# Line_Reader.net
KiCad netlist of a schematic drawn in Altium Designer
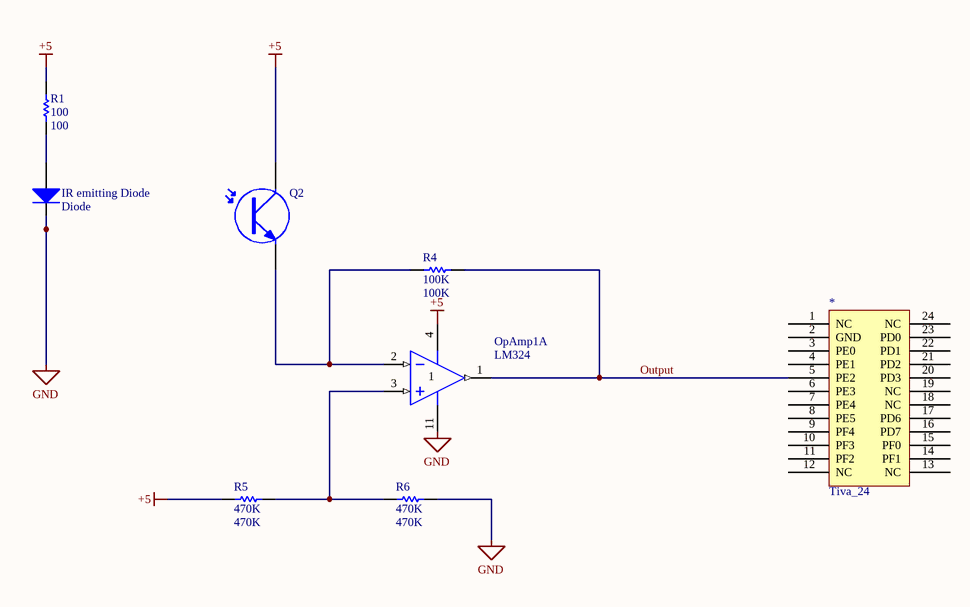
[diagram p0: Line  Reader.SchDoc]

(export (version "E")
  (design (tool "Eeschema 10.0.6"))
  (components
    (comp (ref "*")
      (value "Tiva_24")
      (description "Tiva Protection 24 Pin Connector")
      (libsource (lib "ME218_BaseLib") (part "Tiva_24"))
    )
    (comp (ref "IR emitting Diode")
      (value "Diode")
      (footprint "DSO-C2/X3.3")
      (description "Default Diode")
      (fields
        (field (name "MANUFACTURER") "Generic Components")
        (field (name "PUBLISHER") "Altium Hobart Technology Centre")
      )
      (libsource (lib "ME218_BaseLib") (part "Diode"))
    )
    (comp (ref "OpAmp1")
      (value "LM324")
      (footprint "DIP-14")
      (description "Low-Power Quad Operational Amplifier")
      (fields
        (field (name "MANUFACTURER") "National Semiconductor")
        (field (name "PUBLISHER") "Altium Hobart Technology Centre")
      )
      (libsource (lib "ME218_BaseLib") (part "LM324AJ"))
    )
    (comp (ref "Q2")
      (value "LTR 3208")
      (footprint "SFM-T2(3)/X1.6V")
      (description "NPN Phototransistor")
      (fields (field (name "MANUFACTURER") "Generic Components"))
      (libsource (lib "ME218_BaseLib") (part "Photo NPN"))
    )
    (comp (ref "R1")
      (value "100")
      (footprint "AXIAL-0.3")
      (description "Resistor")
      (fields
        (field (name "MANUFACTURER") "Generic Components")
        (field (name "ALTIUM_VALUE") "100")
        (field (name "PUBLISHER") "Altium Hobart Technology Centre")
      )
      (libsource (lib "ME218_BaseLib") (part "Res1"))
    )
    (comp (ref "R4")
      (value "100K")
      (footprint "AXIAL-0.3")
      (description "Resistor")
      (fields
        (field (name "MANUFACTURER") "Generic Components")
        (field (name "ALTIUM_VALUE") "100K")
        (field (name "PUBLISHER") "Altium Hobart Technology Centre")
      )
      (libsource (lib "ME218_BaseLib") (part "Res1"))
    )
    (comp (ref "R5")
      (value "470K")
      (footprint "AXIAL-0.3")
      (description "Resistor")
      (fields
        (field (name "MANUFACTURER") "Generic Components")
        (field (name "ALTIUM_VALUE") "470K")
        (field (name "PUBLISHER") "Altium Hobart Technology Centre")
      )
      (libsource (lib "ME218_BaseLib") (part "Res1"))
    )
    (comp (ref "R6")
      (value "470K")
      (footprint "AXIAL-0.3")
      (description "Resistor")
      (fields
        (field (name "MANUFACTURER") "Generic Components")
        (field (name "ALTIUM_VALUE") "470K")
        (field (name "PUBLISHER") "Altium Hobart Technology Centre")
      )
      (libsource (lib "ME218_BaseLib") (part "Res1"))
    )
  )
  (nets
    (net (code "1") (name "+5") (class "Default")
      (node (ref "OpAmp1") (pin "4") (pinfunction "V+_4") (pintype "power_in"))
      (node (ref "Q2") (pin "1") (pinfunction "C_1") (pintype "passive"))
      (node (ref "R1") (pin "2") (pinfunction "2_2") (pintype "passive"))
      (node (ref "R5") (pin "1") (pinfunction "1_1") (pintype "passive"))
    )
    (net (code "2") (name "/Output") (class "Default")
      (node (ref "*") (pin "5") (pinfunction "PE2_5") (pintype "passive"))
      (node (ref "OpAmp1") (pin "1") (pinfunction "OUT_1") (pintype "output"))
      (node (ref "R4") (pin "2") (pinfunction "2_2") (pintype "passive"))
    )
    (net (code "3") (name "GND") (class "Default")
      (node (ref "IR emitting Diode") (pin "2") (pinfunction "K_2") (pintype "passive"))
      (node (ref "OpAmp1") (pin "11") (pinfunction "GND_11") (pintype "power_in"))
      (node (ref "R6") (pin "2") (pinfunction "2_2") (pintype "passive"))
    )
    (net (code "4") (name "Net-(IR emitting Diode-A)") (class "Default")
      (node (ref "IR emitting Diode") (pin "1") (pinfunction "A_1") (pintype "passive"))
      (node (ref "R1") (pin "1") (pinfunction "1_1") (pintype "passive"))
    )
    (net (code "5") (name "Net-(OpAmp1A-IN+)") (class "Default")
      (node (ref "OpAmp1") (pin "3") (pinfunction "IN+_3") (pintype "input"))
      (node (ref "R5") (pin "2") (pinfunction "2_2") (pintype "passive"))
      (node (ref "R6") (pin "1") (pinfunction "1_1") (pintype "passive"))
    )
    (net (code "6") (name "Net-(OpAmp1A-IN-)") (class "Default")
      (node (ref "OpAmp1") (pin "2") (pinfunction "IN-_2") (pintype "input"))
      (node (ref "Q2") (pin "3") (pinfunction "E_3") (pintype "passive"))
      (node (ref "R4") (pin "1") (pinfunction "1_1") (pintype "passive"))
    )
    (net (code "7") (name "unconnected-(*-GND-Pad2)") (class "Default")
      (node (ref "*") (pin "2") (pinfunction "GND_2") (pintype "passive"))
    )
    (net (code "8") (name "unconnected-(*-NC-Pad1)") (class "Default")
      (node (ref "*") (pin "1") (pinfunction "NC_1") (pintype "passive"))
    )
    (net (code "9") (name "unconnected-(*-NC-Pad12)") (class "Default")
      (node (ref "*") (pin "12") (pinfunction "NC_12") (pintype "passive"))
    )
    (net (code "10") (name "unconnected-(*-NC-Pad13)") (class "Default")
      (node (ref "*") (pin "13") (pinfunction "NC_13") (pintype "passive"))
    )
    (net (code "11") (name "unconnected-(*-NC-Pad18)") (class "Default")
      (node (ref "*") (pin "18") (pinfunction "NC_18") (pintype "passive"))
    )
    (net (code "12") (name "unconnected-(*-NC-Pad19)") (class "Default")
      (node (ref "*") (pin "19") (pinfunction "NC_19") (pintype "passive"))
    )
    (net (code "13") (name "unconnected-(*-NC-Pad24)") (class "Default")
      (node (ref "*") (pin "24") (pinfunction "NC_24") (pintype "passive"))
    )
    (net (code "14") (name "unconnected-(*-PD0-Pad23)") (class "Default")
      (node (ref "*") (pin "23") (pinfunction "PD0_23") (pintype "passive"))
    )
    (net (code "15") (name "unconnected-(*-PD1-Pad22)") (class "Default")
      (node (ref "*") (pin "22") (pinfunction "PD1_22") (pintype "passive"))
    )
    (net (code "16") (name "unconnected-(*-PD2-Pad21)") (class "Default")
      (node (ref "*") (pin "21") (pinfunction "PD2_21") (pintype "passive"))
    )
    (net (code "17") (name "unconnected-(*-PD3-Pad20)") (class "Default")
      (node (ref "*") (pin "20") (pinfunction "PD3_20") (pintype "passive"))
    )
    (net (code "18") (name "unconnected-(*-PD6-Pad17)") (class "Default")
      (node (ref "*") (pin "17") (pinfunction "PD6_17") (pintype "passive"))
    )
    (net (code "19") (name "unconnected-(*-PD7-Pad16)") (class "Default")
      (node (ref "*") (pin "16") (pinfunction "PD7_16") (pintype "passive"))
    )
    (net (code "20") (name "unconnected-(*-PE0-Pad3)") (class "Default")
      (node (ref "*") (pin "3") (pinfunction "PE0_3") (pintype "passive"))
    )
    (net (code "21") (name "unconnected-(*-PE1-Pad4)") (class "Default")
      (node (ref "*") (pin "4") (pinfunction "PE1_4") (pintype "passive"))
    )
    (net (code "22") (name "unconnected-(*-PE3-Pad6)") (class "Default")
      (node (ref "*") (pin "6") (pinfunction "PE3_6") (pintype "passive"))
    )
    (net (code "23") (name "unconnected-(*-PE4-Pad7)") (class "Default")
      (node (ref "*") (pin "7") (pinfunction "PE4_7") (pintype "passive"))
    )
    (net (code "24") (name "unconnected-(*-PE5-Pad8)") (class "Default")
      (node (ref "*") (pin "8") (pinfunction "PE5_8") (pintype "passive"))
    )
    (net (code "25") (name "unconnected-(*-PF0-Pad15)") (class "Default")
      (node (ref "*") (pin "15") (pinfunction "PF0_15") (pintype "passive"))
    )
    (net (code "26") (name "unconnected-(*-PF1-Pad14)") (class "Default")
      (node (ref "*") (pin "14") (pinfunction "PF1_14") (pintype "passive"))
    )
    (net (code "27") (name "unconnected-(*-PF2-Pad11)") (class "Default")
      (node (ref "*") (pin "11") (pinfunction "PF2_11") (pintype "passive"))
    )
    (net (code "28") (name "unconnected-(*-PF3-Pad10)") (class "Default")
      (node (ref "*") (pin "10") (pinfunction "PF3_10") (pintype "passive"))
    )
    (net (code "29") (name "unconnected-(*-PF4-Pad9)") (class "Default")
      (node (ref "*") (pin "9") (pinfunction "PF4_9") (pintype "passive"))
    )
  )
)
